# drv.net
KiCad netlist of a schematic drawn in EAGLE
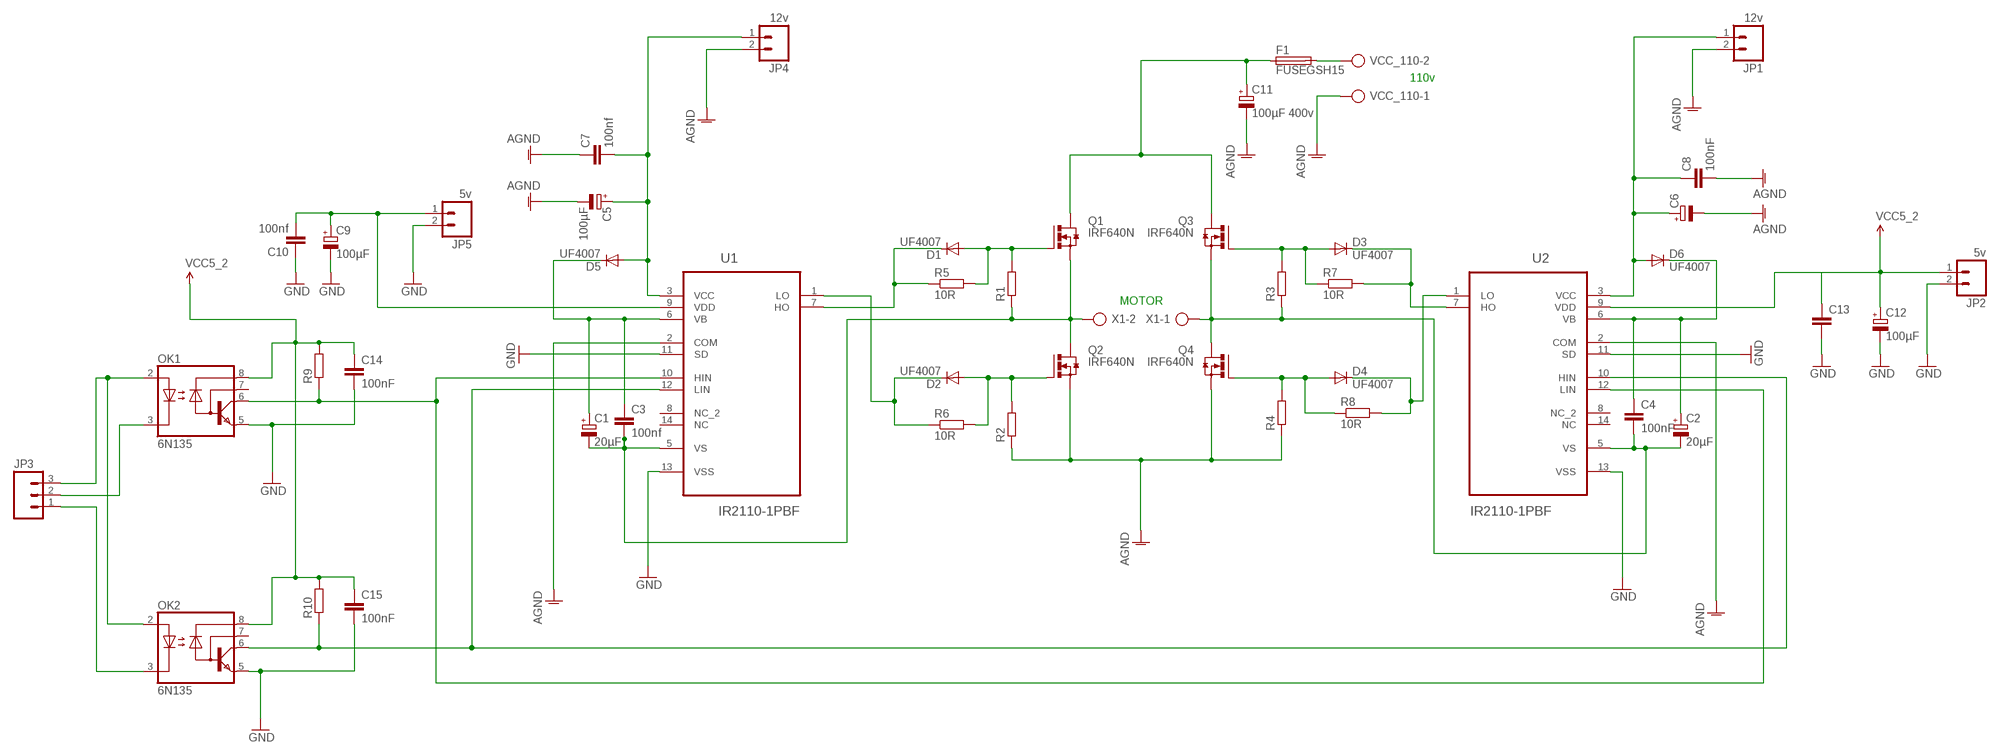
[diagram p0: schematic, sheet 1]

(export (version "E")
  (design (tool "Eeschema 10.0.6"))
  (components
    (comp (ref "C1")
      (value "20µF")
      (footprint "eagle-import:E2,5-6E")
      (libsource (lib "eagle-import") (part "CPOL-EUE2,5-6E"))
    )
    (comp (ref "C2")
      (value "20µF")
      (footprint "eagle-import:E2,5-6E")
      (libsource (lib "eagle-import") (part "CPOL-EUE2,5-6E"))
    )
    (comp (ref "C3")
      (value "100nf")
      (footprint "eagle-import:C0805")
      (libsource (lib "eagle-import") (part "C-EUC0805"))
    )
    (comp (ref "C4")
      (value "100nF")
      (footprint "eagle-import:C0504")
      (libsource (lib "eagle-import") (part "C-EUC0504"))
    )
    (comp (ref "C5")
      (value "100µF")
      (footprint "eagle-import:E2-5")
      (libsource (lib "eagle-import") (part "CPOL-EUE2-5"))
    )
    (comp (ref "C6")
      (value "CPOL-EUE2-5")
      (footprint "eagle-import:E2-5")
      (libsource (lib "eagle-import") (part "CPOL-EUE2-5"))
    )
    (comp (ref "C7")
      (value "100nf")
      (footprint "eagle-import:C1310")
      (libsource (lib "eagle-import") (part "C-EUC1310"))
    )
    (comp (ref "C8")
      (value "100nF")
      (footprint "eagle-import:C0805")
      (libsource (lib "eagle-import") (part "C-EUC0805"))
    )
    (comp (ref "C9")
      (value "100µF")
      (footprint "eagle-import:E2-5")
      (libsource (lib "eagle-import") (part "CPOL-EUE2-5"))
    )
    (comp (ref "C10")
      (value "100nf")
      (footprint "eagle-import:C0805")
      (libsource (lib "eagle-import") (part "C-EUC0805"))
    )
    (comp (ref "C11")
      (value "100µF 400v")
      (footprint "eagle-import:EB25D")
      (libsource (lib "eagle-import") (part "CPOL-EUE10-25"))
    )
    (comp (ref "C12")
      (value "100µF")
      (footprint "eagle-import:E2-5")
      (libsource (lib "eagle-import") (part "CPOL-EUE2-5"))
    )
    (comp (ref "C13")
      (value "C-EUC0805")
      (footprint "eagle-import:C0805")
      (libsource (lib "eagle-import") (part "C-EUC0805"))
    )
    (comp (ref "C14")
      (value "100nF")
      (footprint "eagle-import:C0805")
      (libsource (lib "eagle-import") (part "C-EUC0805"))
    )
    (comp (ref "C15")
      (value "100nF")
      (footprint "eagle-import:C0805")
      (libsource (lib "eagle-import") (part "C-EUC0805"))
    )
    (comp (ref "D1")
      (value "UF4007")
      (footprint "eagle-import:DIODE-1N4001-KIT")
      (libsource (lib "eagle-import") (part "DIODE"))
    )
    (comp (ref "D2")
      (value "UF4007")
      (footprint "eagle-import:DIODE-1N4001-KIT")
      (libsource (lib "eagle-import") (part "DIODE"))
    )
    (comp (ref "D3")
      (value "UF4007")
      (footprint "eagle-import:DIODE-1N4001-KIT")
      (libsource (lib "eagle-import") (part "DIODE"))
    )
    (comp (ref "D4")
      (value "UF4007")
      (footprint "eagle-import:DIODE-1N4001-KIT")
      (libsource (lib "eagle-import") (part "DIODE"))
    )
    (comp (ref "D5")
      (value "UF4007")
      (footprint "eagle-import:DIODE-1N4001-KIT")
      (libsource (lib "eagle-import") (part "DIODE"))
    )
    (comp (ref "D6")
      (value "UF4007")
      (footprint "eagle-import:DIODE-1N4001-KIT")
      (libsource (lib "eagle-import") (part "DIODE"))
    )
    (comp (ref "F1")
      (value "FUSEGSH15")
      (footprint "eagle-import:GSH15")
      (libsource (lib "eagle-import") (part "FUSEGSH15"))
    )
    (comp (ref "JP1")
      (value "12v")
      (footprint "eagle-import:JST-2-PTH-VERT")
      (libsource (lib "eagle-import") (part "M02JST-PTH-VERT"))
    )
    (comp (ref "JP2")
      (value "5v")
      (footprint "eagle-import:JST-2-PTH-VERT")
      (libsource (lib "eagle-import") (part "M02JST-PTH-VERT"))
    )
    (comp (ref "JP3")
      (value "M03LOCK")
      (footprint "eagle-import:1X03_LOCK")
      (libsource (lib "eagle-import") (part "M03LOCK"))
    )
    (comp (ref "JP4")
      (value "12v")
      (footprint "eagle-import:JST-2-PTH-VERT")
      (libsource (lib "eagle-import") (part "M02JST-PTH-VERT"))
    )
    (comp (ref "JP5")
      (value "5v")
      (footprint "eagle-import:JST-2-PTH-VERT")
      (libsource (lib "eagle-import") (part "M02JST-PTH-VERT"))
    )
    (comp (ref "OK1")
      (value "6N135")
      (footprint "eagle-import:DIL08")
      (fields (field (name "MF") "FAIRCHILD SEMICONDUCTOR"))
      (libsource (lib "eagle-import") (part "6N135"))
    )
    (comp (ref "OK2")
      (value "6N135")
      (footprint "eagle-import:DIL08")
      (fields (field (name "MF") "FAIRCHILD SEMICONDUCTOR"))
      (libsource (lib "eagle-import") (part "6N135"))
    )
    (comp (ref "Q1")
      (value "IRF640N")
      (footprint "eagle-import:TO220AH")
      (libsource (lib "eagle-import") (part "IRF3704"))
    )
    (comp (ref "Q2")
      (value "IRF640N")
      (footprint "eagle-import:TO220AH")
      (libsource (lib "eagle-import") (part "IRF3704"))
    )
    (comp (ref "Q3")
      (value "IRF640N")
      (footprint "eagle-import:TO220AH")
      (libsource (lib "eagle-import") (part "IRF3704"))
    )
    (comp (ref "Q4")
      (value "IRF640N")
      (footprint "eagle-import:TO220AH")
      (libsource (lib "eagle-import") (part "IRF3704"))
    )
    (comp (ref "R1")
      (value "R-EU_0207/12")
      (footprint "eagle-import:0207_12")
      (libsource (lib "eagle-import") (part "R-EU_0207/12"))
    )
    (comp (ref "R2")
      (value "R-EU_0207/12")
      (footprint "eagle-import:0207_12")
      (libsource (lib "eagle-import") (part "R-EU_0207/12"))
    )
    (comp (ref "R3")
      (value "R-EU_0207/12")
      (footprint "eagle-import:0207_12")
      (libsource (lib "eagle-import") (part "R-EU_0207/12"))
    )
    (comp (ref "R4")
      (value "R-EU_0207/12")
      (footprint "eagle-import:0207_12")
      (libsource (lib "eagle-import") (part "R-EU_0207/12"))
    )
    (comp (ref "R5")
      (value "10R")
      (footprint "eagle-import:0207_12")
      (libsource (lib "eagle-import") (part "R-EU_0207/12"))
    )
    (comp (ref "R6")
      (value "10R")
      (footprint "eagle-import:0207_12")
      (libsource (lib "eagle-import") (part "R-EU_0207/12"))
    )
    (comp (ref "R7")
      (value "10R")
      (footprint "eagle-import:0207_12")
      (libsource (lib "eagle-import") (part "R-EU_0207/12"))
    )
    (comp (ref "R8")
      (value "10R")
      (footprint "eagle-import:0207_12")
      (libsource (lib "eagle-import") (part "R-EU_0207/12"))
    )
    (comp (ref "R9")
      (value "R-EU_R0805")
      (footprint "eagle-import:R0805")
      (libsource (lib "eagle-import") (part "R-EU_R0805"))
    )
    (comp (ref "R10")
      (value "R-EU_R0805")
      (footprint "eagle-import:R0805")
      (libsource (lib "eagle-import") (part "R-EU_R0805"))
    )
    (comp (ref "U1")
      (value "IR2110-1PBF")
      (footprint "eagle-import:DIP254P762X533-14")
      (libsource (lib "eagle-import") (part "IR2110-1PBF"))
    )
    (comp (ref "U2")
      (value "IR2110-1PBF")
      (footprint "eagle-import:DIP254P762X533-14")
      (libsource (lib "eagle-import") (part "IR2110-1PBF"))
    )
    (comp (ref "VCC_110")
      (value "AK300/2")
      (footprint "eagle-import:AK300_2")
      (libsource (lib "eagle-import") (part "AK300/2"))
    )
    (comp (ref "X1")
      (value "AK300/2")
      (footprint "eagle-import:AK300_2")
      (libsource (lib "eagle-import") (part "AK300/2"))
    )
  )
  (nets
    (net (code "1") (name "AGND") (class "Default")
      (node (ref "C11") (pin "-") (pinfunction "-_-") (pintype "passive"))
      (node (ref "C5") (pin "-") (pinfunction "-_-") (pintype "passive"))
      (node (ref "C6") (pin "-") (pinfunction "-_-") (pintype "passive"))
      (node (ref "C7") (pin "1") (pinfunction "1_1") (pintype "passive"))
      (node (ref "C8") (pin "2") (pinfunction "2_2") (pintype "passive"))
      (node (ref "JP1") (pin "2") (pinfunction "2_2") (pintype "passive"))
      (node (ref "JP4") (pin "2") (pinfunction "2_2") (pintype "passive"))
      (node (ref "Q2") (pin "E") (pinfunction "S_E") (pintype "passive"))
      (node (ref "Q4") (pin "E") (pinfunction "S_E") (pintype "passive"))
      (node (ref "R2") (pin "1") (pinfunction "1_1") (pintype "passive"))
      (node (ref "R4") (pin "1") (pinfunction "1_1") (pintype "passive"))
      (node (ref "U1") (pin "2") (pinfunction "COM_2") (pintype "passive"))
      (node (ref "U2") (pin "2") (pinfunction "COM_2") (pintype "passive"))
      (node (ref "VCC_110") (pin "1") (pinfunction "KL_1") (pintype "passive"))
    )
    (net (code "2") (name "GND") (class "Default")
      (node (ref "C10") (pin "1") (pinfunction "1_1") (pintype "passive"))
      (node (ref "C12") (pin "-") (pinfunction "-_-") (pintype "passive"))
      (node (ref "C13") (pin "2") (pinfunction "2_2") (pintype "passive"))
      (node (ref "C14") (pin "2") (pinfunction "2_2") (pintype "passive"))
      (node (ref "C15") (pin "2") (pinfunction "2_2") (pintype "passive"))
      (node (ref "C9") (pin "-") (pinfunction "-_-") (pintype "passive"))
      (node (ref "JP2") (pin "2") (pinfunction "2_2") (pintype "passive"))
      (node (ref "JP5") (pin "2") (pinfunction "2_2") (pintype "passive"))
      (node (ref "OK1") (pin "5") (pinfunction "GND_5") (pintype "passive"))
      (node (ref "OK2") (pin "5") (pinfunction "GND_5") (pintype "passive"))
      (node (ref "U1") (pin "11") (pinfunction "SD_11") (pintype "input"))
      (node (ref "U1") (pin "13") (pinfunction "VSS_13") (pintype "power_in"))
      (node (ref "U2") (pin "11") (pinfunction "SD_11") (pintype "input"))
      (node (ref "U2") (pin "13") (pinfunction "VSS_13") (pintype "power_in"))
    )
    (net (code "3") (name "Net-(OK1-A)") (class "Default")
      (node (ref "JP3") (pin "3") (pinfunction "3_3") (pintype "passive"))
      (node (ref "OK1") (pin "2") (pinfunction "A_2") (pintype "passive"))
      (node (ref "OK2") (pin "2") (pinfunction "A_2") (pintype "passive"))
    )
    (net (code "4") (name "Net-(OK1-C)") (class "Default")
      (node (ref "JP3") (pin "2") (pinfunction "2_2") (pintype "passive"))
      (node (ref "OK1") (pin "3") (pinfunction "C_3") (pintype "passive"))
    )
    (net (code "5") (name "Net-(OK1-VO)") (class "Default")
      (node (ref "OK1") (pin "6") (pinfunction "VO_6") (pintype "passive"))
      (node (ref "R9") (pin "1") (pinfunction "1_1") (pintype "passive"))
      (node (ref "U1") (pin "10") (pinfunction "HIN_10") (pintype "input"))
      (node (ref "U2") (pin "12") (pinfunction "LIN_12") (pintype "input"))
    )
    (net (code "6") (name "Net-(OK2-C)") (class "Default")
      (node (ref "JP3") (pin "1") (pinfunction "1_1") (pintype "passive"))
      (node (ref "OK2") (pin "3") (pinfunction "C_3") (pintype "passive"))
    )
    (net (code "7") (name "Net-(OK2-VO)") (class "Default")
      (node (ref "OK2") (pin "6") (pinfunction "VO_6") (pintype "passive"))
      (node (ref "R10") (pin "1") (pinfunction "1_1") (pintype "passive"))
      (node (ref "U1") (pin "12") (pinfunction "LIN_12") (pintype "input"))
      (node (ref "U2") (pin "10") (pinfunction "HIN_10") (pintype "input"))
    )
    (net (code "8") (name "Net-(Q1-D)") (class "Default")
      (node (ref "C11") (pin "+") (pinfunction "+_+") (pintype "passive"))
      (node (ref "F1") (pin "1") (pinfunction "1_1") (pintype "passive"))
      (node (ref "Q1") (pin "C") (pinfunction "D_C") (pintype "passive"))
      (node (ref "Q3") (pin "C") (pinfunction "D_C") (pintype "passive"))
    )
    (net (code "9") (name "Net-(Q1-G)") (class "Default")
      (node (ref "D1") (pin "A") (pinfunction "A_A") (pintype "passive"))
      (node (ref "Q1") (pin "B") (pinfunction "G_B") (pintype "passive"))
      (node (ref "R1") (pin "2") (pinfunction "2_2") (pintype "passive"))
      (node (ref "R5") (pin "2") (pinfunction "2_2") (pintype "passive"))
    )
    (net (code "10") (name "Net-(Q1-S)") (class "Default")
      (node (ref "C1") (pin "-") (pinfunction "-_-") (pintype "passive"))
      (node (ref "C3") (pin "2") (pinfunction "2_2") (pintype "passive"))
      (node (ref "Q1") (pin "E") (pinfunction "S_E") (pintype "passive"))
      (node (ref "Q2") (pin "C") (pinfunction "D_C") (pintype "passive"))
      (node (ref "R1") (pin "1") (pinfunction "1_1") (pintype "passive"))
      (node (ref "U1") (pin "5") (pinfunction "VS_5") (pintype "power_in"))
      (node (ref "X1") (pin "2") (pinfunction "KL_2") (pintype "passive"))
    )
    (net (code "11") (name "Net-(Q2-G)") (class "Default")
      (node (ref "D2") (pin "A") (pinfunction "A_A") (pintype "passive"))
      (node (ref "Q2") (pin "B") (pinfunction "G_B") (pintype "passive"))
      (node (ref "R2") (pin "2") (pinfunction "2_2") (pintype "passive"))
      (node (ref "R6") (pin "2") (pinfunction "2_2") (pintype "passive"))
    )
    (net (code "12") (name "Net-(Q3-G)") (class "Default")
      (node (ref "D3") (pin "A") (pinfunction "A_A") (pintype "passive"))
      (node (ref "Q3") (pin "B") (pinfunction "G_B") (pintype "passive"))
      (node (ref "R3") (pin "2") (pinfunction "2_2") (pintype "passive"))
      (node (ref "R7") (pin "1") (pinfunction "1_1") (pintype "passive"))
    )
    (net (code "13") (name "Net-(Q3-S)") (class "Default")
      (node (ref "C2") (pin "-") (pinfunction "-_-") (pintype "passive"))
      (node (ref "C4") (pin "2") (pinfunction "2_2") (pintype "passive"))
      (node (ref "Q3") (pin "E") (pinfunction "S_E") (pintype "passive"))
      (node (ref "Q4") (pin "C") (pinfunction "D_C") (pintype "passive"))
      (node (ref "R3") (pin "1") (pinfunction "1_1") (pintype "passive"))
      (node (ref "U2") (pin "5") (pinfunction "VS_5") (pintype "power_in"))
      (node (ref "X1") (pin "1") (pinfunction "KL_1") (pintype "passive"))
    )
    (net (code "14") (name "Net-(Q4-G)") (class "Default")
      (node (ref "D4") (pin "A") (pinfunction "A_A") (pintype "passive"))
      (node (ref "Q4") (pin "B") (pinfunction "G_B") (pintype "passive"))
      (node (ref "R4") (pin "2") (pinfunction "2_2") (pintype "passive"))
      (node (ref "R8") (pin "1") (pinfunction "1_1") (pintype "passive"))
    )
    (net (code "15") (name "Net-(U1-HO)") (class "Default")
      (node (ref "D1") (pin "C") (pinfunction "C_C") (pintype "passive"))
      (node (ref "R5") (pin "1") (pinfunction "1_1") (pintype "passive"))
      (node (ref "U1") (pin "7") (pinfunction "HO_7") (pintype "output"))
    )
    (net (code "16") (name "Net-(U1-LO)") (class "Default")
      (node (ref "D2") (pin "C") (pinfunction "C_C") (pintype "passive"))
      (node (ref "R6") (pin "1") (pinfunction "1_1") (pintype "passive"))
      (node (ref "U1") (pin "1") (pinfunction "LO_1") (pintype "output"))
    )
    (net (code "17") (name "Net-(U1-VB)") (class "Default")
      (node (ref "C1") (pin "+") (pinfunction "+_+") (pintype "passive"))
      (node (ref "C3") (pin "1") (pinfunction "1_1") (pintype "passive"))
      (node (ref "D5") (pin "C") (pinfunction "C_C") (pintype "passive"))
      (node (ref "U1") (pin "6") (pinfunction "VB_6") (pintype "power_in"))
    )
    (net (code "18") (name "Net-(U1-VCC)") (class "Default")
      (node (ref "C5") (pin "+") (pinfunction "+_+") (pintype "passive"))
      (node (ref "C7") (pin "2") (pinfunction "2_2") (pintype "passive"))
      (node (ref "D5") (pin "A") (pinfunction "A_A") (pintype "passive"))
      (node (ref "JP4") (pin "1") (pinfunction "1_1") (pintype "passive"))
      (node (ref "U1") (pin "3") (pinfunction "VCC_3") (pintype "power_in"))
    )
    (net (code "19") (name "Net-(U1-VDD)") (class "Default")
      (node (ref "C10") (pin "2") (pinfunction "2_2") (pintype "passive"))
      (node (ref "C9") (pin "+") (pinfunction "+_+") (pintype "passive"))
      (node (ref "JP5") (pin "1") (pinfunction "1_1") (pintype "passive"))
      (node (ref "U1") (pin "9") (pinfunction "VDD_9") (pintype "power_in"))
    )
    (net (code "20") (name "Net-(U2-HO)") (class "Default")
      (node (ref "D3") (pin "C") (pinfunction "C_C") (pintype "passive"))
      (node (ref "R7") (pin "2") (pinfunction "2_2") (pintype "passive"))
      (node (ref "U2") (pin "7") (pinfunction "HO_7") (pintype "output"))
    )
    (net (code "21") (name "Net-(U2-LO)") (class "Default")
      (node (ref "D4") (pin "C") (pinfunction "C_C") (pintype "passive"))
      (node (ref "R8") (pin "2") (pinfunction "2_2") (pintype "passive"))
      (node (ref "U2") (pin "1") (pinfunction "LO_1") (pintype "output"))
    )
    (net (code "22") (name "Net-(U2-VB)") (class "Default")
      (node (ref "C2") (pin "+") (pinfunction "+_+") (pintype "passive"))
      (node (ref "C4") (pin "1") (pinfunction "1_1") (pintype "passive"))
      (node (ref "D6") (pin "C") (pinfunction "C_C") (pintype "passive"))
      (node (ref "U2") (pin "6") (pinfunction "VB_6") (pintype "power_in"))
    )
    (net (code "23") (name "Net-(U2-VCC)") (class "Default")
      (node (ref "C6") (pin "+") (pinfunction "+_+") (pintype "passive"))
      (node (ref "C8") (pin "1") (pinfunction "1_1") (pintype "passive"))
      (node (ref "D6") (pin "A") (pinfunction "A_A") (pintype "passive"))
      (node (ref "JP1") (pin "1") (pinfunction "1_1") (pintype "passive"))
      (node (ref "U2") (pin "3") (pinfunction "VCC_3") (pintype "power_in"))
    )
    (net (code "24") (name "Net-(VCC_110B-KL)") (class "Default")
      (node (ref "F1") (pin "2") (pinfunction "2_2") (pintype "passive"))
      (node (ref "VCC_110") (pin "2") (pinfunction "KL_2") (pintype "passive"))
    )
    (net (code "25") (name "VCC5_2") (class "Default")
      (node (ref "C12") (pin "+") (pinfunction "+_+") (pintype "passive"))
      (node (ref "C13") (pin "1") (pinfunction "1_1") (pintype "passive"))
      (node (ref "C14") (pin "1") (pinfunction "1_1") (pintype "passive"))
      (node (ref "C15") (pin "1") (pinfunction "1_1") (pintype "passive"))
      (node (ref "JP2") (pin "1") (pinfunction "1_1") (pintype "passive"))
      (node (ref "OK1") (pin "8") (pinfunction "VCC_8") (pintype "passive"))
      (node (ref "OK2") (pin "8") (pinfunction "VCC_8") (pintype "passive"))
      (node (ref "R10") (pin "2") (pinfunction "2_2") (pintype "passive"))
      (node (ref "R9") (pin "2") (pinfunction "2_2") (pintype "passive"))
      (node (ref "U2") (pin "9") (pinfunction "VDD_9") (pintype "power_in"))
    )
    (net (code "26") (name "unconnected-(OK1-VB-Pad7)") (class "Default")
      (node (ref "OK1") (pin "7") (pinfunction "VB_7") (pintype "passive"))
    )
    (net (code "27") (name "unconnected-(OK2-VB-Pad7)") (class "Default")
      (node (ref "OK2") (pin "7") (pinfunction "VB_7") (pintype "passive"))
    )
    (net (code "28") (name "unconnected-(U1-NC-Pad14)") (class "Default")
      (node (ref "U1") (pin "14") (pinfunction "NC_14") (pintype "no_connect"))
    )
    (net (code "29") (name "unconnected-(U1-NC_2-Pad8)") (class "Default")
      (node (ref "U1") (pin "8") (pinfunction "NC_2_8") (pintype "no_connect"))
    )
    (net (code "30") (name "unconnected-(U2-NC-Pad14)") (class "Default")
      (node (ref "U2") (pin "14") (pinfunction "NC_14") (pintype "no_connect"))
    )
    (net (code "31") (name "unconnected-(U2-NC_2-Pad8)") (class "Default")
      (node (ref "U2") (pin "8") (pinfunction "NC_2_8") (pintype "no_connect"))
    )
  )
)
